# Zio_Qwiic_Adapter.net
KiCad netlist of a schematic drawn in EAGLE
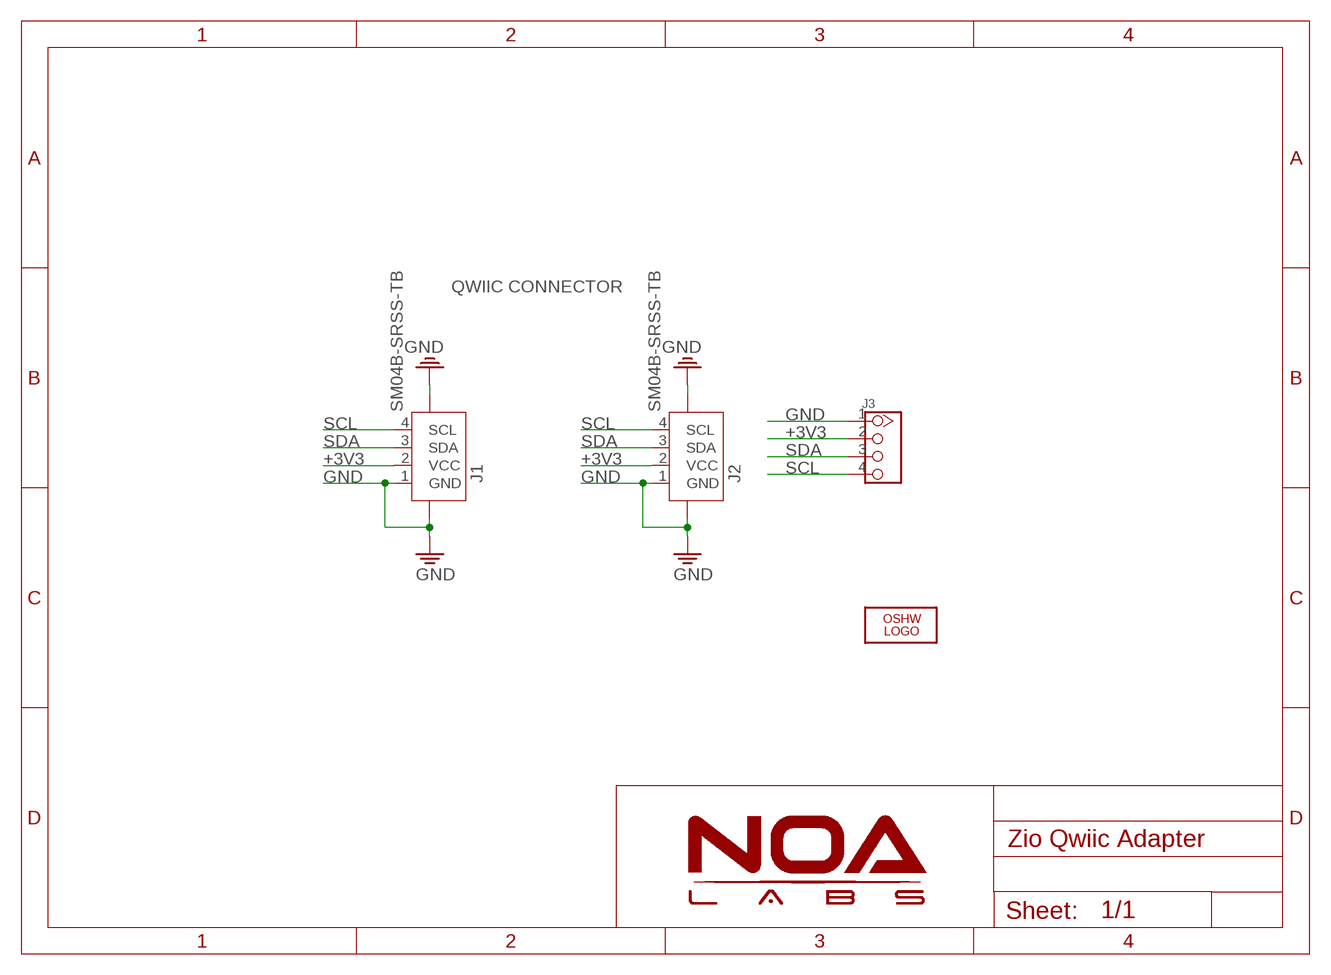
[diagram p0: schematic, sheet 1]

(export (version "E")
  (design (tool "Eeschema 10.0.6"))
  (components
    (comp (ref "J1")
      (value "SM04B-SRSS-TB")
      (footprint "eagle-import:JST-SH-4P")
      (libsource (lib "eagle-import") (part "JST-SH-4P-1.0"))
    )
    (comp (ref "J2")
      (value "SM04B-SRSS-TB")
      (footprint "eagle-import:JST-SH-4P")
      (libsource (lib "eagle-import") (part "JST-SH-4P-1.0"))
    )
    (comp (ref "J3")
      (value "HEADER-4P-80/40MIL")
      (footprint "eagle-import:4P-2.54-80_40MIL")
      (libsource (lib "eagle-import") (part "HEADER-4P-80/40MIL"))
    )
    (comp (ref "LOGO1")
      (value "LOGO-OSHW-6MILX0070-NT")
      (footprint "eagle-import:OSHW_6X70_NOTEXT")
      (libsource (lib "eagle-import") (part "LOGO-OSHW-6MILX0070-NT"))
    )
  )
  (nets
    (net (code "1") (name "/+3V3") (class "Default")
      (node (ref "J1") (pin "2") (pinfunction "VCC_2") (pintype "bidirectional"))
      (node (ref "J2") (pin "2") (pinfunction "VCC_2") (pintype "bidirectional"))
      (node (ref "J3") (pin "2") (pinfunction "P$2_2") (pintype "bidirectional"))
    )
    (net (code "2") (name "/SCL") (class "Default")
      (node (ref "J1") (pin "4") (pinfunction "SCL_4") (pintype "bidirectional"))
      (node (ref "J2") (pin "4") (pinfunction "SCL_4") (pintype "bidirectional"))
      (node (ref "J3") (pin "4") (pinfunction "P$4_4") (pintype "bidirectional"))
    )
    (net (code "3") (name "/SDA") (class "Default")
      (node (ref "J1") (pin "3") (pinfunction "SDA_3") (pintype "bidirectional"))
      (node (ref "J2") (pin "3") (pinfunction "SDA_3") (pintype "bidirectional"))
      (node (ref "J3") (pin "3") (pinfunction "P$3_3") (pintype "bidirectional"))
    )
    (net (code "4") (name "GND") (class "Default")
      (node (ref "J1") (pin "1") (pinfunction "GND_1") (pintype "bidirectional"))
      (node (ref "J1") (pin "NC1") (pinfunction "5_NC1") (pintype "bidirectional"))
      (node (ref "J1") (pin "NC2") (pinfunction "6_NC2") (pintype "bidirectional"))
      (node (ref "J2") (pin "1") (pinfunction "GND_1") (pintype "bidirectional"))
      (node (ref "J2") (pin "NC1") (pinfunction "5_NC1") (pintype "bidirectional"))
      (node (ref "J2") (pin "NC2") (pinfunction "6_NC2") (pintype "bidirectional"))
      (node (ref "J3") (pin "1") (pinfunction "P$1_1") (pintype "bidirectional"))
    )
  )
)
